# 03_PWM_DRIVER.net
KiCad netlist of a schematic drawn in Altium Designer
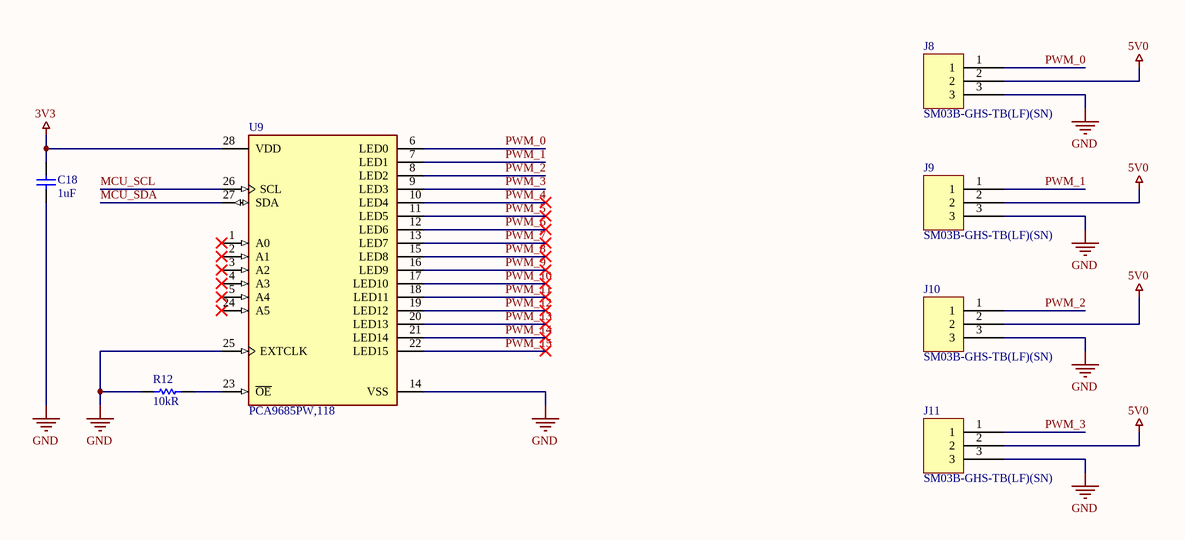
[diagram p0: [03] PWM DRIVER.SchDoc]

(export (version "E")
  (design (tool "Eeschema 10.0.6"))
  (components
    (comp (ref "C18")
      (value "1uF")
      (footprint "INCH 0805 - METRIC 2012 - H140")
      (description "CAP SMD 1uF 25V 10% 0805")
      (fields
        (field (name "MANUFACTURER") "Murata")
        (field (name "MANUFACTURER PART NUMBER") "GCM21BR71E105KA56L")
      )
      (libsource (lib "Capacitors") (part "GCM21BR71E105KA56L"))
    )
    (comp (ref "J8")
      (value "SM03B-GHS-TB(LF)(SN)")
      (footprint "SM03B-GHS-TB(LF)(SN)")
      (description "JST (JAPAN SOLDERLESS TERMINALS) - SM03B-GHS-TB (LF)(SN) - MACHO, 1,25 MM, 3 VÍAS, SMT, 90 GRADOS")
      (fields (field (name "MANUFACTURER") "JST"))
      (libsource (lib "Connectors") (part "SM03B-GHS-TB(LF)(SN)"))
    )
    (comp (ref "J9")
      (value "SM03B-GHS-TB(LF)(SN)")
      (footprint "SM03B-GHS-TB(LF)(SN)")
      (description "JST (JAPAN SOLDERLESS TERMINALS) - SM03B-GHS-TB (LF)(SN) - MACHO, 1,25 MM, 3 VÍAS, SMT, 90 GRADOS")
      (fields (field (name "MANUFACTURER") "JST"))
      (libsource (lib "Connectors") (part "SM03B-GHS-TB(LF)(SN)"))
    )
    (comp (ref "J10")
      (value "SM03B-GHS-TB(LF)(SN)")
      (footprint "SM03B-GHS-TB(LF)(SN)")
      (description "JST (JAPAN SOLDERLESS TERMINALS) - SM03B-GHS-TB (LF)(SN) - MACHO, 1,25 MM, 3 VÍAS, SMT, 90 GRADOS")
      (fields (field (name "MANUFACTURER") "JST"))
      (libsource (lib "Connectors") (part "SM03B-GHS-TB(LF)(SN)"))
    )
    (comp (ref "J11")
      (value "SM03B-GHS-TB(LF)(SN)")
      (footprint "SM03B-GHS-TB(LF)(SN)")
      (description "JST (JAPAN SOLDERLESS TERMINALS) - SM03B-GHS-TB (LF)(SN) - MACHO, 1,25 MM, 3 VÍAS, SMT, 90 GRADOS")
      (fields (field (name "MANUFACTURER") "JST"))
      (libsource (lib "Connectors") (part "SM03B-GHS-TB(LF)(SN)"))
    )
    (comp (ref "R12")
      (value "10kR")
      (footprint "INCH 0805 - METRIC 2012 - H070")
      (description "RES SMD 10kOHM 1% 1/2W 0805")
      (fields
        (field (name "MANUFACTURER") "Panasonic")
        (field (name "MANUFACTURER PART NUMBER") "ERJ-P06F1002V")
      )
      (libsource (lib "Resistors") (part "ERJ-P06F1002V"))
    )
    (comp (ref "U9")
      (value "PCA9685PW,118")
      (footprint "FP-SOT361-1-MFG")
      (description "IC LED DRIVER RGBA 28-TSSOP")
      (fields
        (field (name "MANUFACTURER") "NXP Semiconductors")
        (field (name "OCTOPART") "https://octopart.com/pca9685pw%2C118-nxp+semiconductors-11853435")
      )
      (libsource (lib "Altium Content Vault") (part "50b6f6febb80a1ca83d1eae7256368c"))
    )
  )
  (nets
    (net (code "1") (name "/MCU_SCL") (class "Default")
      (node (ref "U9") (pin "26") (pinfunction "SCL_26") (pintype "input"))
    )
    (net (code "2") (name "/MCU_SDA") (class "Default")
      (node (ref "U9") (pin "27") (pinfunction "SDA_27") (pintype "bidirectional"))
    )
    (net (code "3") (name "/PWM_0") (class "Default")
      (node (ref "J8") (pin "1") (pinfunction "1_1") (pintype "passive"))
      (node (ref "U9") (pin "6") (pinfunction "LED0_6") (pintype "passive"))
    )
    (net (code "4") (name "/PWM_1") (class "Default")
      (node (ref "J9") (pin "1") (pinfunction "1_1") (pintype "passive"))
      (node (ref "U9") (pin "7") (pinfunction "LED1_7") (pintype "passive"))
    )
    (net (code "5") (name "/PWM_2") (class "Default")
      (node (ref "J10") (pin "1") (pinfunction "1_1") (pintype "passive"))
      (node (ref "U9") (pin "8") (pinfunction "LED2_8") (pintype "passive"))
    )
    (net (code "6") (name "/PWM_3") (class "Default")
      (node (ref "J11") (pin "1") (pinfunction "1_1") (pintype "passive"))
      (node (ref "U9") (pin "9") (pinfunction "LED3_9") (pintype "passive"))
    )
    (net (code "7") (name "/PWM_4") (class "Default")
      (node (ref "U9") (pin "10") (pinfunction "LED4_10") (pintype "passive+no_connect"))
    )
    (net (code "8") (name "/PWM_5") (class "Default")
      (node (ref "U9") (pin "11") (pinfunction "LED5_11") (pintype "passive+no_connect"))
    )
    (net (code "9") (name "/PWM_6") (class "Default")
      (node (ref "U9") (pin "12") (pinfunction "LED6_12") (pintype "passive+no_connect"))
    )
    (net (code "10") (name "/PWM_7") (class "Default")
      (node (ref "U9") (pin "13") (pinfunction "LED7_13") (pintype "passive+no_connect"))
    )
    (net (code "11") (name "/PWM_8") (class "Default")
      (node (ref "U9") (pin "15") (pinfunction "LED8_15") (pintype "passive+no_connect"))
    )
    (net (code "12") (name "/PWM_9") (class "Default")
      (node (ref "U9") (pin "16") (pinfunction "LED9_16") (pintype "passive+no_connect"))
    )
    (net (code "13") (name "/PWM_10") (class "Default")
      (node (ref "U9") (pin "17") (pinfunction "LED10_17") (pintype "passive+no_connect"))
    )
    (net (code "14") (name "/PWM_11") (class "Default")
      (node (ref "U9") (pin "18") (pinfunction "LED11_18") (pintype "passive+no_connect"))
    )
    (net (code "15") (name "/PWM_12") (class "Default")
      (node (ref "U9") (pin "19") (pinfunction "LED12_19") (pintype "passive+no_connect"))
    )
    (net (code "16") (name "/PWM_13") (class "Default")
      (node (ref "U9") (pin "20") (pinfunction "LED13_20") (pintype "passive+no_connect"))
    )
    (net (code "17") (name "/PWM_14") (class "Default")
      (node (ref "U9") (pin "21") (pinfunction "LED14_21") (pintype "passive+no_connect"))
    )
    (net (code "18") (name "/PWM_15") (class "Default")
      (node (ref "U9") (pin "22") (pinfunction "LED15_22") (pintype "passive+no_connect"))
    )
    (net (code "19") (name "3V3") (class "Default")
      (node (ref "C18") (pin "2") (pintype "passive"))
      (node (ref "U9") (pin "28") (pinfunction "VDD_28") (pintype "power_in"))
    )
    (net (code "20") (name "5V0") (class "Default")
      (node (ref "J10") (pin "2") (pinfunction "2_2") (pintype "passive"))
      (node (ref "J11") (pin "2") (pinfunction "2_2") (pintype "passive"))
      (node (ref "J8") (pin "2") (pinfunction "2_2") (pintype "passive"))
      (node (ref "J9") (pin "2") (pinfunction "2_2") (pintype "passive"))
    )
    (net (code "21") (name "GND") (class "Default")
      (node (ref "C18") (pin "1") (pintype "passive"))
      (node (ref "J10") (pin "3") (pinfunction "3_3") (pintype "passive"))
      (node (ref "J11") (pin "3") (pinfunction "3_3") (pintype "passive"))
      (node (ref "J8") (pin "3") (pinfunction "3_3") (pintype "passive"))
      (node (ref "J9") (pin "3") (pinfunction "3_3") (pintype "passive"))
      (node (ref "R12") (pin "2") (pintype "passive"))
      (node (ref "U9") (pin "14") (pinfunction "VSS_14") (pintype "power_in"))
      (node (ref "U9") (pin "25") (pinfunction "EXTCLK_25") (pintype "input"))
    )
    (net (code "22") (name "Net-(U9-~{OE})") (class "Default")
      (node (ref "R12") (pin "1") (pintype "passive"))
      (node (ref "U9") (pin "23") (pinfunction "~{OE}_23") (pintype "input"))
    )
    (net (code "23") (name "unconnected-(U9-A0-Pad1)") (class "Default")
      (node (ref "U9") (pin "1") (pinfunction "A0_1") (pintype "input+no_connect"))
    )
    (net (code "24") (name "unconnected-(U9-A1-Pad2)") (class "Default")
      (node (ref "U9") (pin "2") (pinfunction "A1_2") (pintype "input+no_connect"))
    )
    (net (code "25") (name "unconnected-(U9-A2-Pad3)") (class "Default")
      (node (ref "U9") (pin "3") (pinfunction "A2_3") (pintype "input+no_connect"))
    )
    (net (code "26") (name "unconnected-(U9-A3-Pad4)") (class "Default")
      (node (ref "U9") (pin "4") (pinfunction "A3_4") (pintype "input+no_connect"))
    )
    (net (code "27") (name "unconnected-(U9-A4-Pad5)") (class "Default")
      (node (ref "U9") (pin "5") (pinfunction "A4_5") (pintype "input+no_connect"))
    )
    (net (code "28") (name "unconnected-(U9-A5-Pad24)") (class "Default")
      (node (ref "U9") (pin "24") (pinfunction "A5_24") (pintype "input+no_connect"))
    )
  )
)
